# 51__2020-06-08_13-22-36.net
KiCad netlist of a schematic drawn in Altium Designer
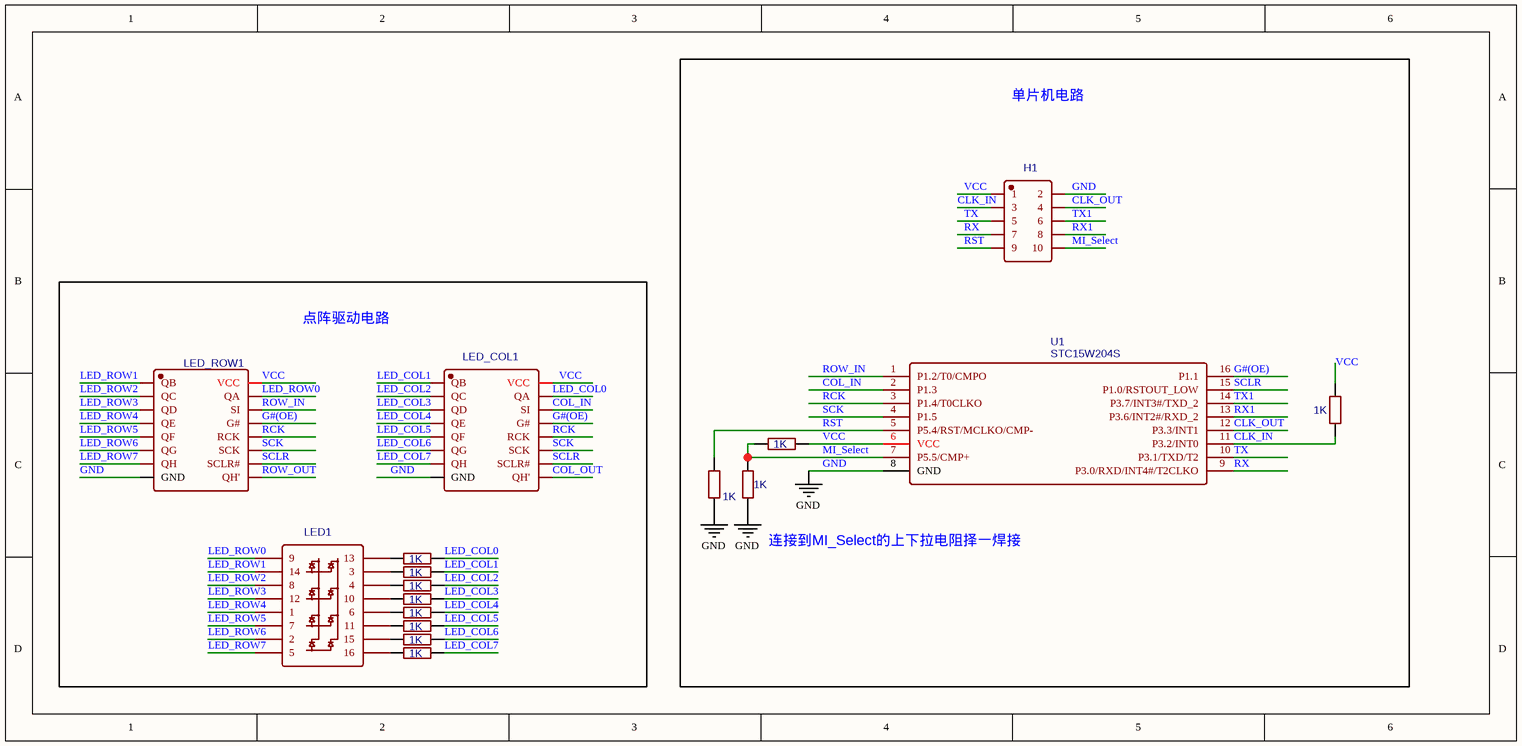
[diagram p0: 51版_2020-06-08_13-22-36.schdoc]

(export (version "E")
  (design (tool "Eeschema 10.0.6"))
  (components
    (comp (ref "H1")
      (value "Female header2.54mm2*5p Straight")
      (fields (field (name "BOM_SUPPLIER PART") "C30419"))
      (libsource (lib "altium-import") (part "root_0_Female header2.54mm2*5p Straight_"))
    )
    (comp (ref "LED1")
      (value "SLD1388DRA1GD")
      (fields (field (name "BOM_SUPPLIER PART") "C225991") (field (name "CONTRIBUTOR") "LCSC"))
      (libsource (lib "altium-import") (part "root_0_SLD1388DRA1GD_"))
    )
    (comp (ref "LED_COL1")
      (value "74HC595D_C431479")
      (fields
        (field (name "BOM_SUPPLIER PART") "C431479")
        (field (name "BOM_MANUFACTURER PART") "74HC595D")
        (field (name "CONTRIBUTOR") "LCSC")
      )
      (libsource (lib "altium-import") (part "root_0_74HC595D_C431479_"))
    )
    (comp (ref "LED_ROW1")
      (value "74HC595D_C431479")
      (fields
        (field (name "BOM_SUPPLIER PART") "C431479")
        (field (name "BOM_MANUFACTURER PART") "74HC595D")
        (field (name "CONTRIBUTOR") "LCSC")
      )
      (libsource (lib "altium-import") (part "root_0_74HC595D_C431479_"))
    )
    (comp (ref "R1")
      (value "1K")
      (fields
        (field (name "BOM_MANUFACTURER PART") "0603WAF1001T5E")
        (field (name "BOM_SUPPLIER PART") "C21190")
      )
      (libsource (lib "altium-import") (part "root_0_1K_"))
    )
    (comp (ref "R2")
      (value "1K")
      (fields
        (field (name "BOM_MANUFACTURER PART") "0603WAF1001T5E")
        (field (name "BOM_SUPPLIER PART") "C21190")
      )
      (libsource (lib "altium-import") (part "root_0_1K_"))
    )
    (comp (ref "R3")
      (value "1K")
      (fields
        (field (name "BOM_MANUFACTURER PART") "0603WAF1001T5E")
        (field (name "BOM_SUPPLIER PART") "C21190")
      )
      (libsource (lib "altium-import") (part "root_0_1K_"))
    )
    (comp (ref "R4")
      (value "1K")
      (fields
        (field (name "BOM_MANUFACTURER PART") "0603WAF1001T5E")
        (field (name "BOM_SUPPLIER PART") "C21190")
      )
      (libsource (lib "altium-import") (part "root_0_1K_"))
    )
    (comp (ref "R5")
      (value "1K")
      (fields
        (field (name "BOM_MANUFACTURER PART") "0603WAF1001T5E")
        (field (name "BOM_SUPPLIER PART") "C21190")
      )
      (libsource (lib "altium-import") (part "root_0_1K_"))
    )
    (comp (ref "R6")
      (value "1K")
      (fields
        (field (name "BOM_MANUFACTURER PART") "0603WAF1001T5E")
        (field (name "BOM_SUPPLIER PART") "C21190")
      )
      (libsource (lib "altium-import") (part "root_0_1K_"))
    )
    (comp (ref "R7")
      (value "1K")
      (fields
        (field (name "BOM_MANUFACTURER PART") "0603WAF1001T5E")
        (field (name "BOM_SUPPLIER PART") "C21190")
      )
      (libsource (lib "altium-import") (part "root_0_1K_"))
    )
    (comp (ref "R8")
      (value "1K")
      (fields
        (field (name "BOM_MANUFACTURER PART") "0603WAF1001T5E")
        (field (name "BOM_SUPPLIER PART") "C21190")
      )
      (libsource (lib "altium-import") (part "root_0_1K_"))
    )
    (comp (ref "R9")
      (value "1K")
      (fields
        (field (name "BOM_MANUFACTURER PART") "0603WAF1001T5E")
        (field (name "BOM_SUPPLIER PART") "C21190")
      )
      (libsource (lib "altium-import") (part "root_1_1K_"))
    )
    (comp (ref "R10")
      (value "1K")
      (fields
        (field (name "BOM_MANUFACTURER PART") "0603WAF1001T5E")
        (field (name "BOM_SUPPLIER PART") "C21190")
      )
      (libsource (lib "altium-import") (part "root_1_1K_"))
    )
    (comp (ref "R11")
      (value "1K")
      (fields
        (field (name "BOM_MANUFACTURER PART") "0603WAF1001T5E")
        (field (name "BOM_SUPPLIER PART") "C21190")
      )
      (libsource (lib "altium-import") (part "root_2_1K_"))
    )
    (comp (ref "R12")
      (value "1K")
      (fields
        (field (name "BOM_MANUFACTURER PART") "0603WAF1001T5E")
        (field (name "BOM_SUPPLIER PART") "C21190")
      )
      (libsource (lib "altium-import") (part "root_1_1K_"))
    )
    (comp (ref "U1")
      (value "STC15W204S")
      (fields (field (name "BOM_SUPPLIER PART") "C20068") (field (name "CONTRIBUTOR") "LCSC"))
      (libsource (lib "altium-import") (part "root_0_STC15W204S_"))
    )
  )
  (nets
    (net (code "1") (name "/CLK_IN") (class "Default")
      (node (ref "H1") (pin "3") (pinfunction "3_3") (pintype "passive"))
      (node (ref "R12") (pin "1") (pinfunction "1_1") (pintype "passive"))
      (node (ref "U1") (pin "11") (pinfunction "P3.2/INT0_11") (pintype "passive"))
    )
    (net (code "2") (name "/CLK_OUT") (class "Default")
      (node (ref "H1") (pin "4") (pinfunction "4_4") (pintype "passive"))
      (node (ref "U1") (pin "12") (pinfunction "P3.3/INT1_12") (pintype "passive"))
    )
    (net (code "3") (name "/COL_IN") (class "Default")
      (node (ref "LED_COL1") (pin "14") (pinfunction "SI_14") (pintype "passive"))
      (node (ref "U1") (pin "2") (pinfunction "P1.3_2") (pintype "passive"))
    )
    (net (code "4") (name "/COL_OUT") (class "Default")
      (node (ref "LED_COL1") (pin "9") (pinfunction "QH'_9") (pintype "passive"))
    )
    (net (code "5") (name "/G#(OE)") (class "Default")
      (node (ref "LED_COL1") (pin "13") (pinfunction "G#_13") (pintype "passive"))
      (node (ref "LED_ROW1") (pin "13") (pinfunction "G#_13") (pintype "passive"))
      (node (ref "U1") (pin "16") (pinfunction "P1.1_16") (pintype "passive"))
    )
    (net (code "6") (name "/LED_COL0") (class "Default")
      (node (ref "LED_COL1") (pin "15") (pinfunction "QA_15") (pintype "passive"))
      (node (ref "R2") (pin "2") (pinfunction "2_2") (pintype "passive"))
    )
    (net (code "7") (name "/LED_COL1") (class "Default")
      (node (ref "LED_COL1") (pin "1") (pinfunction "QB_1") (pintype "passive"))
      (node (ref "R1") (pin "2") (pinfunction "2_2") (pintype "passive"))
    )
    (net (code "8") (name "/LED_COL2") (class "Default")
      (node (ref "LED_COL1") (pin "2") (pinfunction "QC_2") (pintype "passive"))
      (node (ref "R3") (pin "2") (pinfunction "2_2") (pintype "passive"))
    )
    (net (code "9") (name "/LED_COL3") (class "Default")
      (node (ref "LED_COL1") (pin "3") (pinfunction "QD_3") (pintype "passive"))
      (node (ref "R4") (pin "2") (pinfunction "2_2") (pintype "passive"))
    )
    (net (code "10") (name "/LED_COL4") (class "Default")
      (node (ref "LED_COL1") (pin "4") (pinfunction "QE_4") (pintype "passive"))
      (node (ref "R5") (pin "2") (pinfunction "2_2") (pintype "passive"))
    )
    (net (code "11") (name "/LED_COL5") (class "Default")
      (node (ref "LED_COL1") (pin "5") (pinfunction "QF_5") (pintype "passive"))
      (node (ref "R6") (pin "2") (pinfunction "2_2") (pintype "passive"))
    )
    (net (code "12") (name "/LED_COL6") (class "Default")
      (node (ref "LED_COL1") (pin "6") (pinfunction "QG_6") (pintype "passive"))
      (node (ref "R7") (pin "2") (pinfunction "2_2") (pintype "passive"))
    )
    (net (code "13") (name "/LED_COL7") (class "Default")
      (node (ref "LED_COL1") (pin "7") (pinfunction "QH_7") (pintype "passive"))
      (node (ref "R8") (pin "2") (pinfunction "2_2") (pintype "passive"))
    )
    (net (code "14") (name "/LED_ROW0") (class "Default")
      (node (ref "LED1") (pin "9") (pinfunction "9_9") (pintype "passive"))
      (node (ref "LED_ROW1") (pin "15") (pinfunction "QA_15") (pintype "passive"))
    )
    (net (code "15") (name "/LED_ROW1") (class "Default")
      (node (ref "LED1") (pin "14") (pinfunction "14_14") (pintype "passive"))
      (node (ref "LED_ROW1") (pin "1") (pinfunction "QB_1") (pintype "passive"))
    )
    (net (code "16") (name "/LED_ROW2") (class "Default")
      (node (ref "LED1") (pin "8") (pinfunction "8_8") (pintype "passive"))
      (node (ref "LED_ROW1") (pin "2") (pinfunction "QC_2") (pintype "passive"))
    )
    (net (code "17") (name "/LED_ROW3") (class "Default")
      (node (ref "LED1") (pin "12") (pinfunction "12_12") (pintype "passive"))
      (node (ref "LED_ROW1") (pin "3") (pinfunction "QD_3") (pintype "passive"))
    )
    (net (code "18") (name "/LED_ROW4") (class "Default")
      (node (ref "LED1") (pin "1") (pinfunction "1_1") (pintype "passive"))
      (node (ref "LED_ROW1") (pin "4") (pinfunction "QE_4") (pintype "passive"))
    )
    (net (code "19") (name "/LED_ROW5") (class "Default")
      (node (ref "LED1") (pin "7") (pinfunction "7_7") (pintype "passive"))
      (node (ref "LED_ROW1") (pin "5") (pinfunction "QF_5") (pintype "passive"))
    )
    (net (code "20") (name "/LED_ROW6") (class "Default")
      (node (ref "LED1") (pin "2") (pinfunction "2_2") (pintype "passive"))
      (node (ref "LED_ROW1") (pin "6") (pinfunction "QG_6") (pintype "passive"))
    )
    (net (code "21") (name "/LED_ROW7") (class "Default")
      (node (ref "LED1") (pin "5") (pinfunction "5_5") (pintype "passive"))
      (node (ref "LED_ROW1") (pin "7") (pinfunction "QH_7") (pintype "passive"))
    )
    (net (code "22") (name "/MI_Select") (class "Default")
      (node (ref "H1") (pin "10") (pinfunction "10_10") (pintype "passive"))
      (node (ref "R10") (pin "2") (pinfunction "2_2") (pintype "passive"))
      (node (ref "R11") (pin "2") (pinfunction "2_2") (pintype "passive"))
      (node (ref "U1") (pin "7") (pinfunction "P5.5/CMP+_7") (pintype "passive"))
    )
    (net (code "23") (name "/RCK") (class "Default")
      (node (ref "LED_COL1") (pin "12") (pinfunction "RCK_12") (pintype "passive"))
      (node (ref "LED_ROW1") (pin "12") (pinfunction "RCK_12") (pintype "passive"))
      (node (ref "U1") (pin "3") (pinfunction "P1.4/T0CLKO_3") (pintype "passive"))
    )
    (net (code "24") (name "/ROW_IN") (class "Default")
      (node (ref "LED_ROW1") (pin "14") (pinfunction "SI_14") (pintype "passive"))
      (node (ref "U1") (pin "1") (pinfunction "P1.2/T0/CMPO_1") (pintype "passive"))
    )
    (net (code "25") (name "/ROW_OUT") (class "Default")
      (node (ref "LED_ROW1") (pin "9") (pinfunction "QH'_9") (pintype "passive"))
    )
    (net (code "26") (name "/RST") (class "Default")
      (node (ref "H1") (pin "9") (pinfunction "9_9") (pintype "passive"))
      (node (ref "R9") (pin "2") (pinfunction "2_2") (pintype "passive"))
      (node (ref "U1") (pin "5") (pinfunction "P5.4/RST/MCLKO/CMP-_5") (pintype "passive"))
    )
    (net (code "27") (name "/RX") (class "Default")
      (node (ref "H1") (pin "7") (pinfunction "7_7") (pintype "passive"))
      (node (ref "U1") (pin "9") (pinfunction "P3.0/RXD/INT4#/T2CLKO_9") (pintype "passive"))
    )
    (net (code "28") (name "/RX1") (class "Default")
      (node (ref "H1") (pin "8") (pinfunction "8_8") (pintype "passive"))
      (node (ref "U1") (pin "13") (pinfunction "P3.6/INT2#/RXD_2_13") (pintype "passive"))
    )
    (net (code "29") (name "/SCK") (class "Default")
      (node (ref "LED_COL1") (pin "11") (pinfunction "SCK_11") (pintype "passive"))
      (node (ref "LED_ROW1") (pin "11") (pinfunction "SCK_11") (pintype "passive"))
      (node (ref "U1") (pin "4") (pinfunction "P1.5_4") (pintype "passive"))
    )
    (net (code "30") (name "/SCLR") (class "Default")
      (node (ref "LED_COL1") (pin "10") (pinfunction "SCLR#_10") (pintype "passive"))
      (node (ref "LED_ROW1") (pin "10") (pinfunction "SCLR#_10") (pintype "passive"))
      (node (ref "U1") (pin "15") (pinfunction "P1.0/RSTOUT_LOW_15") (pintype "passive"))
    )
    (net (code "31") (name "/TX") (class "Default")
      (node (ref "H1") (pin "5") (pinfunction "5_5") (pintype "passive"))
      (node (ref "U1") (pin "10") (pinfunction "P3.1/TXD/T2_10") (pintype "passive"))
    )
    (net (code "32") (name "/TX1") (class "Default")
      (node (ref "H1") (pin "6") (pinfunction "6_6") (pintype "passive"))
      (node (ref "U1") (pin "14") (pinfunction "P3.7/INT3#/TXD_2_14") (pintype "passive"))
    )
    (net (code "33") (name "/VCC") (class "Default")
      (node (ref "H1") (pin "1") (pinfunction "1_1") (pintype "passive"))
      (node (ref "LED_COL1") (pin "16") (pinfunction "VCC_16") (pintype "passive"))
      (node (ref "LED_ROW1") (pin "16") (pinfunction "VCC_16") (pintype "passive"))
      (node (ref "R11") (pin "1") (pinfunction "1_1") (pintype "passive"))
      (node (ref "R12") (pin "2") (pinfunction "2_2") (pintype "passive"))
      (node (ref "U1") (pin "6") (pinfunction "VCC_6") (pintype "passive"))
    )
    (net (code "34") (name "GND") (class "Default")
      (node (ref "H1") (pin "2") (pinfunction "2_2") (pintype "passive"))
      (node (ref "LED_COL1") (pin "8") (pinfunction "GND_8") (pintype "passive"))
      (node (ref "LED_ROW1") (pin "8") (pinfunction "GND_8") (pintype "passive"))
      (node (ref "R10") (pin "1") (pinfunction "1_1") (pintype "passive"))
      (node (ref "R9") (pin "1") (pinfunction "1_1") (pintype "passive"))
      (node (ref "U1") (pin "8") (pinfunction "GND_8") (pintype "passive"))
    )
    (net (code "35") (name "Net-(LED1-Pad3)") (class "Default")
      (node (ref "LED1") (pin "3") (pinfunction "3_3") (pintype "passive"))
      (node (ref "R1") (pin "1") (pinfunction "1_1") (pintype "passive"))
    )
    (net (code "36") (name "Net-(LED1-Pad4)") (class "Default")
      (node (ref "LED1") (pin "4") (pinfunction "4_4") (pintype "passive"))
      (node (ref "R3") (pin "1") (pinfunction "1_1") (pintype "passive"))
    )
    (net (code "37") (name "Net-(LED1-Pad6)") (class "Default")
      (node (ref "LED1") (pin "6") (pinfunction "6_6") (pintype "passive"))
      (node (ref "R5") (pin "1") (pinfunction "1_1") (pintype "passive"))
    )
    (net (code "38") (name "Net-(LED1-Pad10)") (class "Default")
      (node (ref "LED1") (pin "10") (pinfunction "10_10") (pintype "passive"))
      (node (ref "R4") (pin "1") (pinfunction "1_1") (pintype "passive"))
    )
    (net (code "39") (name "Net-(LED1-Pad11)") (class "Default")
      (node (ref "LED1") (pin "11") (pinfunction "11_11") (pintype "passive"))
      (node (ref "R6") (pin "1") (pinfunction "1_1") (pintype "passive"))
    )
    (net (code "40") (name "Net-(LED1-Pad13)") (class "Default")
      (node (ref "LED1") (pin "13") (pinfunction "13_13") (pintype "passive"))
      (node (ref "R2") (pin "1") (pinfunction "1_1") (pintype "passive"))
    )
    (net (code "41") (name "Net-(LED1-Pad15)") (class "Default")
      (node (ref "LED1") (pin "15") (pinfunction "15_15") (pintype "passive"))
      (node (ref "R7") (pin "1") (pinfunction "1_1") (pintype "passive"))
    )
    (net (code "42") (name "Net-(LED1-Pad16)") (class "Default")
      (node (ref "LED1") (pin "16") (pinfunction "16_16") (pintype "passive"))
      (node (ref "R8") (pin "1") (pinfunction "1_1") (pintype "passive"))
    )
  )
)
